# snc98_3x4_Switch-futuba.net
KiCad netlist of a schematic drawn in EAGLE
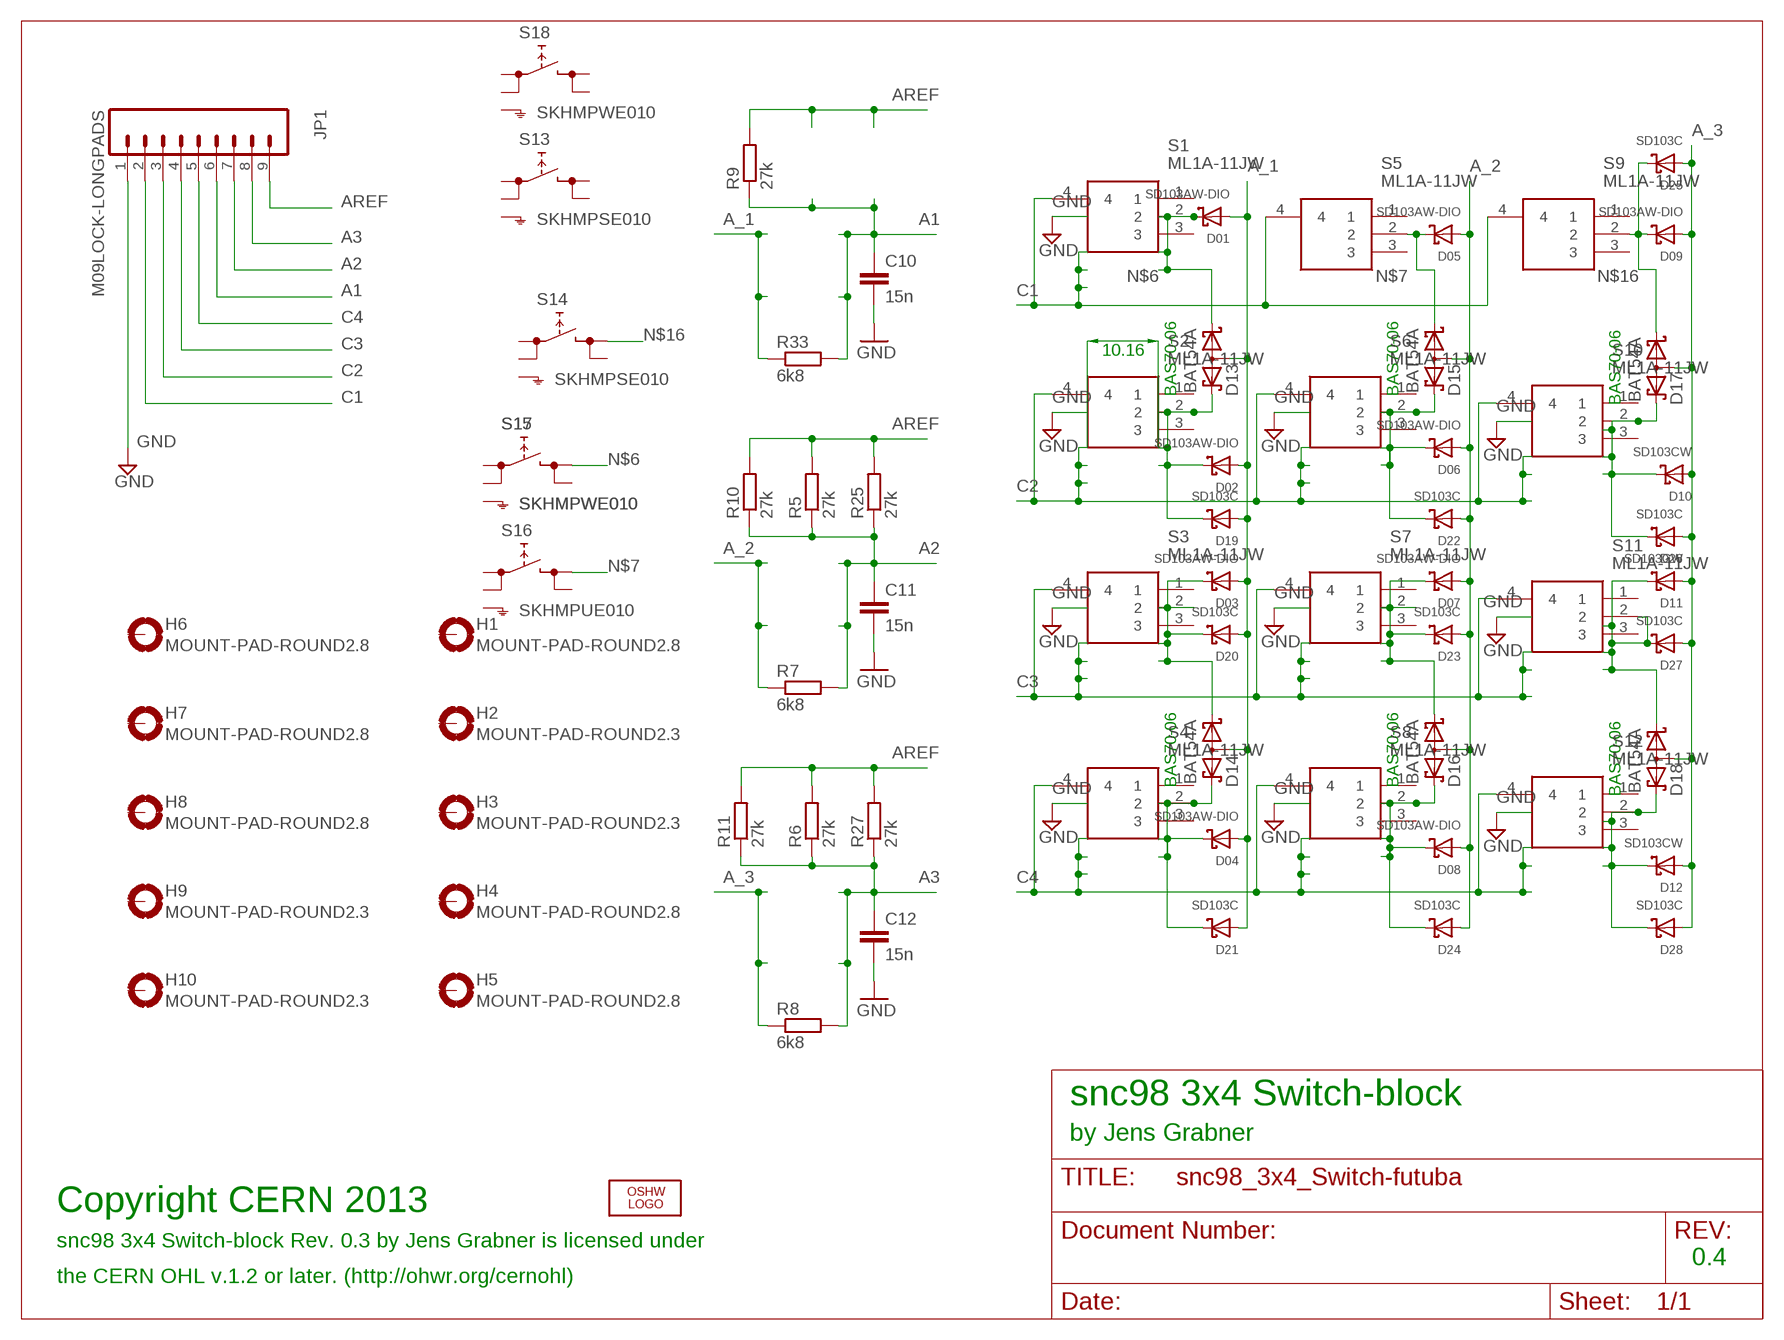
[diagram p0: schematic, sheet 1]

(export (version "E")
  (design (tool "Eeschema 10.0.6"))
  (components
    (comp (ref "C10")
      (value "15n")
      (footprint "eagle-import:C1206K")
      (libsource (lib "eagle-import") (part "C-EUC1206K"))
    )
    (comp (ref "C11")
      (value "15n")
      (footprint "eagle-import:C1206K")
      (libsource (lib "eagle-import") (part "C-EUC1206K"))
    )
    (comp (ref "C12")
      (value "15n")
      (footprint "eagle-import:C1206K")
      (libsource (lib "eagle-import") (part "C-EUC1206K"))
    )
    (comp (ref "D01")
      (value "SD103AW-DIO")
      (footprint "eagle-import:SOD-123F")
      (fields (field (name "MF") "MULTICOMP") (field (name "MPN") "SD103CW-7-F"))
      (libsource (lib "eagle-import") (part "DIODESOD-123F"))
    )
    (comp (ref "D02")
      (value "SD103AW-DIO")
      (footprint "eagle-import:SOD-123F")
      (fields (field (name "MF") "MULTICOMP") (field (name "MPN") "SD103CW-7-F"))
      (libsource (lib "eagle-import") (part "DIODESOD-123F"))
    )
    (comp (ref "D03")
      (value "SD103AW-DIO")
      (footprint "eagle-import:SOD-123F")
      (fields (field (name "MF") "MULTICOMP") (field (name "MPN") "SD103CW-7-F"))
      (libsource (lib "eagle-import") (part "DIODESOD-123F"))
    )
    (comp (ref "D04")
      (value "SD103AW-DIO")
      (footprint "eagle-import:SOD-123F")
      (fields (field (name "MF") "MULTICOMP") (field (name "MPN") "SD103CW-7-F"))
      (libsource (lib "eagle-import") (part "DIODESOD-123F"))
    )
    (comp (ref "D05")
      (value "SD103AW-DIO")
      (footprint "eagle-import:SOD-123F")
      (fields (field (name "MF") "MULTICOMP") (field (name "MPN") "SD103CW-7-F"))
      (libsource (lib "eagle-import") (part "DIODESOD-123F"))
    )
    (comp (ref "D06")
      (value "SD103AW-DIO")
      (footprint "eagle-import:SOD-123F")
      (fields (field (name "MF") "MULTICOMP") (field (name "MPN") "SD103CW-7-F"))
      (libsource (lib "eagle-import") (part "DIODESOD-123F"))
    )
    (comp (ref "D07")
      (value "SD103AW-DIO")
      (footprint "eagle-import:SOD-123F")
      (fields (field (name "MF") "MULTICOMP") (field (name "MPN") "SD103CW-7-F"))
      (libsource (lib "eagle-import") (part "DIODESOD-123F"))
    )
    (comp (ref "D08")
      (value "SD103AW-DIO")
      (footprint "eagle-import:SOD-123F")
      (fields (field (name "MF") "MULTICOMP") (field (name "MPN") "SD103CW-7-F"))
      (libsource (lib "eagle-import") (part "DIODESOD-123F"))
    )
    (comp (ref "D09")
      (value "SD103AW-DIO")
      (footprint "eagle-import:SOD-123F")
      (fields (field (name "MF") "MULTICOMP") (field (name "MPN") "SD103CW-7-F"))
      (libsource (lib "eagle-import") (part "DIODESOD-123F"))
    )
    (comp (ref "D10")
      (value "SD103CW")
      (footprint "eagle-import:SOD-123F")
      (fields (field (name "MF") "MULTICOMP") (field (name "MPN") "SD103CW-7-F"))
      (libsource (lib "eagle-import") (part "DIODESOD-123F"))
    )
    (comp (ref "D11")
      (value "SD103CW")
      (footprint "eagle-import:SOD-123F")
      (fields (field (name "MF") "MULTICOMP") (field (name "MPN") "SD103CW-7-F"))
      (libsource (lib "eagle-import") (part "DIODESOD-123F"))
    )
    (comp (ref "D12")
      (value "SD103CW")
      (footprint "eagle-import:SOD-123F")
      (fields (field (name "MF") "MULTICOMP") (field (name "MPN") "SD103CW-7-F"))
      (libsource (lib "eagle-import") (part "DIODESOD-123F"))
    )
    (comp (ref "D13")
      (value "BAT54A")
      (footprint "eagle-import:SOT23")
      (libsource (lib "eagle-import") (part "BAT54A"))
    )
    (comp (ref "D14")
      (value "BAT54A")
      (footprint "eagle-import:SOT23")
      (libsource (lib "eagle-import") (part "BAT54A"))
    )
    (comp (ref "D15")
      (value "BAT54A")
      (footprint "eagle-import:SOT23")
      (libsource (lib "eagle-import") (part "BAT54A"))
    )
    (comp (ref "D16")
      (value "BAT54A")
      (footprint "eagle-import:SOT23")
      (libsource (lib "eagle-import") (part "BAT54A"))
    )
    (comp (ref "D17")
      (value "BAT54A")
      (footprint "eagle-import:SOT23")
      (libsource (lib "eagle-import") (part "BAT54A"))
    )
    (comp (ref "D18")
      (value "BAT54A")
      (footprint "eagle-import:SOT23")
      (libsource (lib "eagle-import") (part "BAT54A"))
    )
    (comp (ref "D19")
      (value "SD103C")
      (footprint "eagle-import:280MIL-TH")
      (fields (field (name "MF") "MULTICOMP") (field (name "MPN") "SD103CW-7-F"))
      (libsource (lib "eagle-import") (part "DIODE280MIL-TH"))
    )
    (comp (ref "D20")
      (value "SD103C")
      (footprint "eagle-import:280MIL-TH")
      (fields (field (name "MF") "MULTICOMP") (field (name "MPN") "SD103CW-7-F"))
      (libsource (lib "eagle-import") (part "DIODE280MIL-TH"))
    )
    (comp (ref "D21")
      (value "SD103C")
      (footprint "eagle-import:280MIL-TH")
      (fields (field (name "MF") "MULTICOMP") (field (name "MPN") "SD103CW-7-F"))
      (libsource (lib "eagle-import") (part "DIODE280MIL-TH"))
    )
    (comp (ref "D22")
      (value "SD103C")
      (footprint "eagle-import:280MIL-TH")
      (fields (field (name "MF") "MULTICOMP") (field (name "MPN") "SD103CW-7-F"))
      (libsource (lib "eagle-import") (part "DIODE280MIL-TH"))
    )
    (comp (ref "D23")
      (value "SD103C")
      (footprint "eagle-import:280MIL-TH")
      (fields (field (name "MF") "MULTICOMP") (field (name "MPN") "SD103CW-7-F"))
      (libsource (lib "eagle-import") (part "DIODE280MIL-TH"))
    )
    (comp (ref "D24")
      (value "SD103C")
      (footprint "eagle-import:280MIL-TH")
      (fields (field (name "MF") "MULTICOMP") (field (name "MPN") "SD103CW-7-F"))
      (libsource (lib "eagle-import") (part "DIODE280MIL-TH"))
    )
    (comp (ref "D25")
      (value "SD103C")
      (footprint "eagle-import:280MIL-TH")
      (fields (field (name "MF") "MULTICOMP") (field (name "MPN") "SD103CW-7-F"))
      (libsource (lib "eagle-import") (part "DIODE280MIL-TH"))
    )
    (comp (ref "D26")
      (value "SD103C")
      (footprint "eagle-import:280MIL-TH")
      (fields (field (name "MF") "MULTICOMP") (field (name "MPN") "SD103CW-7-F"))
      (libsource (lib "eagle-import") (part "DIODE280MIL-TH"))
    )
    (comp (ref "D27")
      (value "SD103C")
      (footprint "eagle-import:280MIL-TH")
      (fields (field (name "MF") "MULTICOMP") (field (name "MPN") "SD103CW-7-F"))
      (libsource (lib "eagle-import") (part "DIODE280MIL-TH"))
    )
    (comp (ref "D28")
      (value "SD103C")
      (footprint "eagle-import:280MIL-TH")
      (fields (field (name "MF") "MULTICOMP") (field (name "MPN") "SD103CW-7-F"))
      (libsource (lib "eagle-import") (part "DIODE280MIL-TH"))
    )
    (comp (ref "H1")
      (value "MOUNT-PAD-ROUND2.8")
      (footprint "eagle-import:2,8-PAD")
      (libsource (lib "eagle-import") (part "MOUNT-PAD-ROUND2.8"))
    )
    (comp (ref "H2")
      (value "MOUNT-PAD-ROUND2.3")
      (footprint "eagle-import:2,3-PAD")
      (libsource (lib "eagle-import") (part "MOUNT-PAD-ROUND2.3"))
    )
    (comp (ref "H3")
      (value "MOUNT-PAD-ROUND2.3")
      (footprint "eagle-import:2,3-PAD")
      (libsource (lib "eagle-import") (part "MOUNT-PAD-ROUND2.3"))
    )
    (comp (ref "H4")
      (value "MOUNT-PAD-ROUND2.8")
      (footprint "eagle-import:2,8-PAD")
      (libsource (lib "eagle-import") (part "MOUNT-PAD-ROUND2.8"))
    )
    (comp (ref "H5")
      (value "MOUNT-PAD-ROUND2.8")
      (footprint "eagle-import:2,8-PAD")
      (libsource (lib "eagle-import") (part "MOUNT-PAD-ROUND2.8"))
    )
    (comp (ref "H6")
      (value "MOUNT-PAD-ROUND2.8")
      (footprint "eagle-import:2,8-PAD")
      (libsource (lib "eagle-import") (part "MOUNT-PAD-ROUND2.8"))
    )
    (comp (ref "H7")
      (value "MOUNT-PAD-ROUND2.8")
      (footprint "eagle-import:2,8-PAD")
      (libsource (lib "eagle-import") (part "MOUNT-PAD-ROUND2.8"))
    )
    (comp (ref "H8")
      (value "MOUNT-PAD-ROUND2.8")
      (footprint "eagle-import:2,8-PAD")
      (libsource (lib "eagle-import") (part "MOUNT-PAD-ROUND2.8"))
    )
    (comp (ref "H9")
      (value "MOUNT-PAD-ROUND2.3")
      (footprint "eagle-import:2,3-PAD")
      (libsource (lib "eagle-import") (part "MOUNT-PAD-ROUND2.3"))
    )
    (comp (ref "H10")
      (value "MOUNT-PAD-ROUND2.3")
      (footprint "eagle-import:2,3-PAD")
      (libsource (lib "eagle-import") (part "MOUNT-PAD-ROUND2.3"))
    )
    (comp (ref "JP1")
      (value "M09LOCK-LONGPADS")
      (footprint "eagle-import:1X09_LOCK_LONGPADS")
      (libsource (lib "eagle-import") (part "M09LOCK-LONGPADS"))
    )
    (comp (ref "LOGO1")
      (value "OSHW_LOGO_8MILX0150-NT")
      (footprint "eagle-import:OSHW_8X150_NOTEXT")
      (libsource (lib "eagle-import") (part "OSHW_LOGO_8MILX0150-NT"))
    )
    (comp (ref "R5")
      (value "27k")
      (footprint "eagle-import:R1206")
      (libsource (lib "eagle-import") (part "R-EU_R1206"))
    )
    (comp (ref "R6")
      (value "27k")
      (footprint "eagle-import:R1206")
      (libsource (lib "eagle-import") (part "R-EU_R1206"))
    )
    (comp (ref "R7")
      (value "6k8")
      (footprint "eagle-import:M0805")
      (libsource (lib "eagle-import") (part "R-EU_M0805"))
    )
    (comp (ref "R8")
      (value "6k8")
      (footprint "eagle-import:M0805")
      (libsource (lib "eagle-import") (part "R-EU_M0805"))
    )
    (comp (ref "R9")
      (value "27k")
      (footprint "eagle-import:M0805")
      (libsource (lib "eagle-import") (part "R-EU_M0805"))
    )
    (comp (ref "R10")
      (value "27k")
      (footprint "eagle-import:M0805")
      (libsource (lib "eagle-import") (part "R-EU_M0805"))
    )
    (comp (ref "R11")
      (value "27k")
      (footprint "eagle-import:M0805")
      (libsource (lib "eagle-import") (part "R-EU_M0805"))
    )
    (comp (ref "R25")
      (value "27k")
      (footprint "eagle-import:0204_5")
      (libsource (lib "eagle-import") (part "R-EU_0204/5"))
    )
    (comp (ref "R27")
      (value "27k")
      (footprint "eagle-import:0204_5")
      (libsource (lib "eagle-import") (part "R-EU_0204/5"))
    )
    (comp (ref "R33")
      (value "6k8")
      (footprint "eagle-import:M0805")
      (libsource (lib "eagle-import") (part "R-EU_M0805"))
    )
    (comp (ref "S1")
      (value "ML1A-11JW")
      (footprint "eagle-import:ML1A11JW")
      (fields (field (name "MOUSER_PART_NUMBER") "540-ML1A-11JW"))
      (libsource (lib "eagle-import") (part "ML1A-11JW"))
    )
    (comp (ref "S2")
      (value "ML1A-11JW")
      (footprint "eagle-import:ML1A11JW")
      (fields (field (name "MOUSER_PART_NUMBER") "540-ML1A-11JW"))
      (libsource (lib "eagle-import") (part "ML1A-11JW"))
    )
    (comp (ref "S3")
      (value "ML1A-11JW")
      (footprint "eagle-import:ML1A11JW")
      (fields (field (name "MOUSER_PART_NUMBER") "540-ML1A-11JW"))
      (libsource (lib "eagle-import") (part "ML1A-11JW"))
    )
    (comp (ref "S4")
      (value "ML1A-11JW")
      (footprint "eagle-import:ML1A11JW")
      (fields (field (name "MOUSER_PART_NUMBER") "540-ML1A-11JW"))
      (libsource (lib "eagle-import") (part "ML1A-11JW"))
    )
    (comp (ref "S5")
      (value "ML1A-11JW")
      (footprint "eagle-import:ML1A11JW")
      (fields (field (name "MOUSER_PART_NUMBER") "540-ML1A-11JW"))
      (libsource (lib "eagle-import") (part "ML1A-11JW"))
    )
    (comp (ref "S6")
      (value "ML1A-11JW")
      (footprint "eagle-import:ML1A11JW")
      (fields (field (name "MOUSER_PART_NUMBER") "540-ML1A-11JW"))
      (libsource (lib "eagle-import") (part "ML1A-11JW"))
    )
    (comp (ref "S7")
      (value "ML1A-11JW")
      (footprint "eagle-import:ML1A11JW")
      (fields (field (name "MOUSER_PART_NUMBER") "540-ML1A-11JW"))
      (libsource (lib "eagle-import") (part "ML1A-11JW"))
    )
    (comp (ref "S8")
      (value "ML1A-11JW")
      (footprint "eagle-import:ML1A11JW")
      (fields (field (name "MOUSER_PART_NUMBER") "540-ML1A-11JW"))
      (libsource (lib "eagle-import") (part "ML1A-11JW"))
    )
    (comp (ref "S9")
      (value "ML1A-11JW")
      (footprint "eagle-import:ML1A11JW")
      (fields (field (name "MOUSER_PART_NUMBER") "540-ML1A-11JW"))
      (libsource (lib "eagle-import") (part "ML1A-11JW"))
    )
    (comp (ref "S10")
      (value "ML1A-11JW")
      (footprint "eagle-import:ML1A11JW")
      (fields (field (name "MOUSER_PART_NUMBER") "540-ML1A-11JW"))
      (libsource (lib "eagle-import") (part "ML1A-11JW"))
    )
    (comp (ref "S11")
      (value "ML1A-11JW")
      (footprint "eagle-import:ML1A11JW")
      (fields (field (name "MOUSER_PART_NUMBER") "540-ML1A-11JW"))
      (libsource (lib "eagle-import") (part "ML1A-11JW"))
    )
    (comp (ref "S12")
      (value "ML1A-11JW")
      (footprint "eagle-import:ML1A11JW")
      (fields (field (name "MOUSER_PART_NUMBER") "540-ML1A-11JW"))
      (libsource (lib "eagle-import") (part "ML1A-11JW"))
    )
    (comp (ref "S13")
      (value "SKHMPSE010")
      (footprint "eagle-import:SKHMPXE010")
      (libsource (lib "eagle-import") (part "SKHMPE010S"))
    )
    (comp (ref "S14")
      (value "SKHMPSE010")
      (footprint "eagle-import:SKHMPXE010")
      (libsource (lib "eagle-import") (part "SKHMPE010S"))
    )
    (comp (ref "S15")
      (value "SKHMPWE010")
      (footprint "eagle-import:SKHMPXE010")
      (libsource (lib "eagle-import") (part "SKHMPE010W"))
    )
    (comp (ref "S16")
      (value "SKHMPUE010")
      (footprint "eagle-import:SKHMPXE010")
      (libsource (lib "eagle-import") (part "SKHMPE010U"))
    )
    (comp (ref "S17")
      (value "SKHMPWE010")
      (footprint "eagle-import:SKHMPXE010")
      (libsource (lib "eagle-import") (part "SKHMPE010W"))
    )
    (comp (ref "S18")
      (value "SKHMPWE010")
      (footprint "eagle-import:SKHMPXE010")
      (libsource (lib "eagle-import") (part "SKHMPE010W"))
    )
  )
  (nets
    (net (code "1") (name "/A1") (class "Default")
      (node (ref "C10") (pin "1") (pinfunction "1_1") (pintype "passive"))
      (node (ref "JP1") (pin "6") (pinfunction "6_6") (pintype "passive"))
      (node (ref "R33") (pin "2") (pinfunction "2_2") (pintype "passive"))
      (node (ref "R9") (pin "1") (pinfunction "1_1") (pintype "passive"))
    )
    (net (code "2") (name "/A2") (class "Default")
      (node (ref "C11") (pin "1") (pinfunction "1_1") (pintype "passive"))
      (node (ref "JP1") (pin "7") (pinfunction "7_7") (pintype "passive"))
      (node (ref "R10") (pin "1") (pinfunction "1_1") (pintype "passive"))
      (node (ref "R25") (pin "1") (pinfunction "1_1") (pintype "passive"))
      (node (ref "R5") (pin "1") (pinfunction "1_1") (pintype "passive"))
      (node (ref "R7") (pin "2") (pinfunction "2_2") (pintype "passive"))
    )
    (net (code "3") (name "/A3") (class "Default")
      (node (ref "C12") (pin "1") (pinfunction "1_1") (pintype "passive"))
      (node (ref "JP1") (pin "8") (pinfunction "8_8") (pintype "passive"))
      (node (ref "R11") (pin "1") (pinfunction "1_1") (pintype "passive"))
      (node (ref "R27") (pin "1") (pinfunction "1_1") (pintype "passive"))
      (node (ref "R6") (pin "1") (pinfunction "1_1") (pintype "passive"))
      (node (ref "R8") (pin "2") (pinfunction "2_2") (pintype "passive"))
    )
    (net (code "4") (name "/AREF") (class "Default")
      (node (ref "JP1") (pin "9") (pinfunction "9_9") (pintype "passive"))
      (node (ref "R10") (pin "2") (pinfunction "2_2") (pintype "passive"))
      (node (ref "R11") (pin "2") (pinfunction "2_2") (pintype "passive"))
      (node (ref "R25") (pin "2") (pinfunction "2_2") (pintype "passive"))
      (node (ref "R27") (pin "2") (pinfunction "2_2") (pintype "passive"))
      (node (ref "R5") (pin "2") (pinfunction "2_2") (pintype "passive"))
      (node (ref "R6") (pin "2") (pinfunction "2_2") (pintype "passive"))
      (node (ref "R9") (pin "2") (pinfunction "2_2") (pintype "passive"))
    )
    (net (code "5") (name "/A_1") (class "Default")
      (node (ref "D01") (pin "A") (pinfunction "A_A") (pintype "passive"))
      (node (ref "D02") (pin "A") (pinfunction "A_A") (pintype "passive"))
      (node (ref "D03") (pin "A") (pinfunction "A_A") (pintype "passive"))
      (node (ref "D04") (pin "A") (pinfunction "A_A") (pintype "passive"))
      (node (ref "D13") (pin "3") (pinfunction "AA_3") (pintype "passive"))
      (node (ref "D14") (pin "3") (pinfunction "AA_3") (pintype "passive"))
      (node (ref "D19") (pin "P$1") (pinfunction "A_P$1") (pintype "passive"))
      (node (ref "D20") (pin "P$1") (pinfunction "A_P$1") (pintype "passive"))
      (node (ref "D21") (pin "P$1") (pinfunction "A_P$1") (pintype "passive"))
      (node (ref "R33") (pin "1") (pinfunction "1_1") (pintype "passive"))
    )
    (net (code "6") (name "/A_2") (class "Default")
      (node (ref "D05") (pin "A") (pinfunction "A_A") (pintype "passive"))
      (node (ref "D06") (pin "A") (pinfunction "A_A") (pintype "passive"))
      (node (ref "D07") (pin "A") (pinfunction "A_A") (pintype "passive"))
      (node (ref "D08") (pin "A") (pinfunction "A_A") (pintype "passive"))
      (node (ref "D15") (pin "3") (pinfunction "AA_3") (pintype "passive"))
      (node (ref "D16") (pin "3") (pinfunction "AA_3") (pintype "passive"))
      (node (ref "D22") (pin "P$1") (pinfunction "A_P$1") (pintype "passive"))
      (node (ref "D23") (pin "P$1") (pinfunction "A_P$1") (pintype "passive"))
      (node (ref "D24") (pin "P$1") (pinfunction "A_P$1") (pintype "passive"))
      (node (ref "R7") (pin "1") (pinfunction "1_1") (pintype "passive"))
    )
    (net (code "7") (name "/A_3") (class "Default")
      (node (ref "D09") (pin "A") (pinfunction "A_A") (pintype "passive"))
      (node (ref "D10") (pin "A") (pinfunction "A_A") (pintype "passive"))
      (node (ref "D11") (pin "A") (pinfunction "A_A") (pintype "passive"))
      (node (ref "D12") (pin "A") (pinfunction "A_A") (pintype "passive"))
      (node (ref "D17") (pin "3") (pinfunction "AA_3") (pintype "passive"))
      (node (ref "D18") (pin "3") (pinfunction "AA_3") (pintype "passive"))
      (node (ref "D25") (pin "P$1") (pinfunction "A_P$1") (pintype "passive"))
      (node (ref "D26") (pin "P$1") (pinfunction "A_P$1") (pintype "passive"))
      (node (ref "D27") (pin "P$1") (pinfunction "A_P$1") (pintype "passive"))
      (node (ref "D28") (pin "P$1") (pinfunction "A_P$1") (pintype "passive"))
      (node (ref "R8") (pin "1") (pinfunction "1_1") (pintype "passive"))
    )
    (net (code "8") (name "/C1") (class "Default")
      (node (ref "JP1") (pin "2") (pinfunction "2_2") (pintype "passive"))
      (node (ref "S1") (pin "4") (pinfunction "4_4") (pintype "bidirectional"))
      (node (ref "S5") (pin "4") (pinfunction "4_4") (pintype "bidirectional"))
      (node (ref "S9") (pin "4") (pinfunction "4_4") (pintype "bidirectional"))
    )
    (net (code "9") (name "/C2") (class "Default")
      (node (ref "JP1") (pin "3") (pinfunction "3_3") (pintype "passive"))
      (node (ref "S10") (pin "4") (pinfunction "4_4") (pintype "bidirectional"))
      (node (ref "S2") (pin "4") (pinfunction "4_4") (pintype "bidirectional"))
      (node (ref "S6") (pin "4") (pinfunction "4_4") (pintype "bidirectional"))
    )
    (net (code "10") (name "/C3") (class "Default")
      (node (ref "JP1") (pin "4") (pinfunction "4_4") (pintype "passive"))
      (node (ref "S11") (pin "4") (pinfunction "4_4") (pintype "bidirectional"))
      (node (ref "S3") (pin "4") (pinfunction "4_4") (pintype "bidirectional"))
      (node (ref "S7") (pin "4") (pinfunction "4_4") (pintype "bidirectional"))
    )
    (net (code "11") (name "/C4") (class "Default")
      (node (ref "JP1") (pin "5") (pinfunction "5_5") (pintype "passive"))
      (node (ref "S12") (pin "4") (pinfunction "4_4") (pintype "bidirectional"))
      (node (ref "S4") (pin "4") (pinfunction "4_4") (pintype "bidirectional"))
      (node (ref "S8") (pin "4") (pinfunction "4_4") (pintype "bidirectional"))
    )
    (net (code "12") (name "/N$6") (class "Default")
      (node (ref "D01") (pin "C") (pinfunction "C_C") (pintype "passive"))
      (node (ref "D13") (pin "1") (pinfunction "K1_1") (pintype "passive"))
      (node (ref "S1") (pin "2") (pinfunction "2_2") (pintype "bidirectional"))
      (node (ref "S15") (pin "3") (pinfunction "2.1_3") (pintype "passive"))
      (node (ref "S17") (pin "3") (pinfunction "2.1_3") (pintype "passive"))
    )
    (net (code "13") (name "/N$7") (class "Default")
      (node (ref "D05") (pin "C") (pinfunction "C_C") (pintype "passive"))
      (node (ref "D15") (pin "1") (pinfunction "K1_1") (pintype "passive"))
      (node (ref "S16") (pin "3") (pinfunction "2.1_3") (pintype "passive"))
      (node (ref "S5") (pin "2") (pinfunction "2_2") (pintype "bidirectional"))
    )
    (net (code "14") (name "/N$16") (class "Default")
      (node (ref "D09") (pin "C") (pinfunction "C_C") (pintype "passive"))
      (node (ref "D17") (pin "1") (pinfunction "K1_1") (pintype "passive"))
      (node (ref "D25") (pin "P$2") (pinfunction "C_P$2") (pintype "passive"))
      (node (ref "S14") (pin "3") (pinfunction "2.1_3") (pintype "passive"))
      (node (ref "S9") (pin "2") (pinfunction "2_2") (pintype "bidirectional"))
    )
    (net (code "15") (name "GND") (class "Default")
      (node (ref "C10") (pin "2") (pinfunction "2_2") (pintype "passive"))
      (node (ref "C11") (pin "2") (pinfunction "2_2") (pintype "passive"))
      (node (ref "C12") (pin "2") (pinfunction "2_2") (pintype "passive"))
      (node (ref "JP1") (pin "1") (pinfunction "1_1") (pintype "passive"))
    )
    (net (code "16") (name "Net-(D13-K2)") (class "Default")
      (node (ref "D02") (pin "C") (pinfunction "C_C") (pintype "passive"))
      (node (ref "D13") (pin "2") (pinfunction "K2_2") (pintype "passive"))
      (node (ref "D19") (pin "P$2") (pinfunction "C_P$2") (pintype "passive"))
      (node (ref "S2") (pin "2") (pinfunction "2_2") (pintype "bidirectional"))
    )
    (net (code "17") (name "Net-(D14-K1)") (class "Default")
      (node (ref "D03") (pin "C") (pinfunction "C_C") (pintype "passive"))
      (node (ref "D14") (pin "1") (pinfunction "K1_1") (pintype "passive"))
      (node (ref "D20") (pin "P$2") (pinfunction "C_P$2") (pintype "passive"))
      (node (ref "S3") (pin "2") (pinfunction "2_2") (pintype "bidirectional"))
    )
    (net (code "18") (name "Net-(D14-K2)") (class "Default")
      (node (ref "D04") (pin "C") (pinfunction "C_C") (pintype "passive"))
      (node (ref "D14") (pin "2") (pinfunction "K2_2") (pintype "passive"))
      (node (ref "D21") (pin "P$2") (pinfunction "C_P$2") (pintype "passive"))
      (node (ref "S4") (pin "2") (pinfunction "2_2") (pintype "bidirectional"))
    )
    (net (code "19") (name "Net-(D15-K2)") (class "Default")
      (node (ref "D06") (pin "C") (pinfunction "C_C") (pintype "passive"))
      (node (ref "D15") (pin "2") (pinfunction "K2_2") (pintype "passive"))
      (node (ref "D22") (pin "P$2") (pinfunction "C_P$2") (pintype "passive"))
      (node (ref "S6") (pin "2") (pinfunction "2_2") (pintype "bidirectional"))
    )
    (net (code "20") (name "Net-(D16-K1)") (class "Default")
      (node (ref "D07") (pin "C") (pinfunction "C_C") (pintype "passive"))
      (node (ref "D16") (pin "1") (pinfunction "K1_1") (pintype "passive"))
      (node (ref "D23") (pin "P$2") (pinfunction "C_P$2") (pintype "passive"))
      (node (ref "S7") (pin "2") (pinfunction "2_2") (pintype "bidirectional"))
    )
    (net (code "21") (name "Net-(D16-K2)") (class "Default")
      (node (ref "D08") (pin "C") (pinfunction "C_C") (pintype "passive"))
      (node (ref "D16") (pin "2") (pinfunction "K2_2") (pintype "passive"))
      (node (ref "D24") (pin "P$2") (pinfunction "C_P$2") (pintype "passive"))
      (node (ref "S8") (pin "2") (pinfunction "2_2") (pintype "bidirectional"))
    )
    (net (code "22") (name "Net-(D17-K2)") (class "Default")
      (node (ref "D10") (pin "C") (pinfunction "C_C") (pintype "passive"))
      (node (ref "D17") (pin "2") (pinfunction "K2_2") (pintype "passive"))
      (node (ref "D26") (pin "P$2") (pinfunction "C_P$2") (pintype "passive"))
      (node (ref "S10") (pin "2") (pinfunction "2_2") (pintype "bidirectional"))
    )
    (net (code "23") (name "Net-(D18-K1)") (class "Default")
      (node (ref "D11") (pin "C") (pinfunction "C_C") (pintype "passive"))
      (node (ref "D18") (pin "1") (pinfunction "K1_1") (pintype "passive"))
      (node (ref "D27") (pin "P$2") (pinfunction "C_P$2") (pintype "passive"))
      (node (ref "S11") (pin "2") (pinfunction "2_2") (pintype "bidirectional"))
    )
    (net (code "24") (name "Net-(D18-K2)") (class "Default")
      (node (ref "D12") (pin "C") (pinfunction "C_C") (pintype "passive"))
      (node (ref "D18") (pin "2") (pinfunction "K2_2") (pintype "passive"))
      (node (ref "D28") (pin "P$2") (pinfunction "C_P$2") (pintype "passive"))
      (node (ref "S12") (pin "2") (pinfunction "2_2") (pintype "bidirectional"))
    )
    (net (code "25") (name "Net-(S15-1.1)") (class "Default")
      (node (ref "S15") (pin "1") (pinfunction "1.1_1") (pintype "passive"))
      (node (ref "S17") (pin "1") (pinfunction "1.1_1") (pintype "passive"))
    )
    (net (code "26") (name "Net-(S15-1.2)") (class "Default")
      (node (ref "S15") (pin "2") (pinfunction "1.2_2") (pintype "passive"))
      (node (ref "S17") (pin "2") (pinfunction "1.2_2") (pintype "passive"))
    )
    (net (code "27") (name "Net-(S15-2.2)") (class "Default")
      (node (ref "S15") (pin "4") (pinfunction "2.2_4") (pintype "passive"))
      (node (ref "S17") (pin "4") (pinfunction "2.2_4") (pintype "passive"))
    )
    (net (code "28") (name "Net-(S15-SH)") (class "Default")
      (node (ref "S15") (pin "5") (pinfunction "SH_5") (pintype "passive"))
      (node (ref "S17") (pin "5") (pinfunction "SH_5") (pintype "passive"))
    )
    (net (code "29") (name "unconnected-(H1-MOUNT-PadB2,8)") (class "Default")
      (node (ref "H1") (pin "B2,8") (pinfunction "MOUNT_B2,8") (pintype "passive"))
    )
    (net (code "30") (name "unconnected-(H2-MOUNT-PadB2,8)") (class "Default")
      (node (ref "H2") (pin "B2,8") (pinfunction "MOUNT_B2,8") (pintype "passive"))
    )
    (net (code "31") (name "unconnected-(H3-MOUNT-PadB2,8)") (class "Default")
      (node (ref "H3") (pin "B2,8") (pinfunction "MOUNT_B2,8") (pintype "passive"))
    )
    (net (code "32") (name "unconnected-(H4-MOUNT-PadB2,8)") (class "Default")
      (node (ref "H4") (pin "B2,8") (pinfunction "MOUNT_B2,8") (pintype "passive"))
    )
    (net (code "33") (name "unconnected-(H5-MOUNT-PadB2,8)") (class "Default")
      (node (ref "H5") (pin "B2,8") (pinfunction "MOUNT_B2,8") (pintype "passive"))
    )
    (net (code "34") (name "unconnected-(H6-MOUNT-PadB2,8)") (class "Default")
      (node (ref "H6") (pin "B2,8") (pinfunction "MOUNT_B2,8") (pintype "passive"))
    )
    (net (code "35") (name "unconnected-(H7-MOUNT-PadB2,8)") (class "Default")
      (node (ref "H7") (pin "B2,8") (pinfunction "MOUNT_B2,8") (pintype "passive"))
    )
    (net (code "36") (name "unconnected-(H8-MOUNT-PadB2,8)") (class "Default")
      (node (ref "H8") (pin "B2,8") (pinfunction "MOUNT_B2,8") (pintype "passive"))
    )
    (net (code "37") (name "unconnected-(H9-MOUNT-PadB2,8)") (class "Default")
      (node (ref "H9") (pin "B2,8") (pinfunction "MOUNT_B2,8") (pintype "passive"))
    )
    (net (code "38") (name "unconnected-(H10-MOUNT-PadB2,8)") (class "Default")
      (node (ref "H10") (pin "B2,8") (pinfunction "MOUNT_B2,8") (pintype "passive"))
    )
    (net (code "39") (name "unconnected-(S1-Pad1)") (class "Default")
      (node (ref "S1") (pin "1") (pinfunction "1_1") (pintype "bidirectional"))
    )
    (net (code "40") (name "unconnected-(S1-Pad3)") (class "Default")
      (node (ref "S1") (pin "3") (pinfunction "3_3") (pintype "bidirectional"))
    )
    (net (code "41") (name "unconnected-(S2-Pad1)") (class "Default")
      (node (ref "S2") (pin "1") (pinfunction "1_1") (pintype "bidirectional"))
    )
    (net (code "42") (name "unconnected-(S2-Pad3)") (class "Default")
      (node (ref "S2") (pin "3") (pinfunction "3_3") (pintype "bidirectional"))
    )
    (net (code "43") (name "unconnected-(S3-Pad1)") (class "Default")
      (node (ref "S3") (pin "1") (pinfunction "1_1") (pintype "bidirectional"))
    )
    (net (code "44") (name "unconnected-(S3-Pad3)") (class "Default")
      (node (ref "S3") (pin "3") (pinfunction "3_3") (pintype "bidirectional"))
    )
    (net (code "45") (name "unconnected-(S4-Pad1)") (class "Default")
      (node (ref "S4") (pin "1") (pinfunction "1_1") (pintype "bidirectional"))
    )
    (net (code "46") (name "unconnected-(S4-Pad3)") (class "Default")
      (node (ref "S4") (pin "3") (pinfunction "3_3") (pintype "bidirectional"))
    )
    (net (code "47") (name "unconnected-(S5-Pad1)") (class "Default")
      (node (ref "S5") (pin "1") (pinfunction "1_1") (pintype "bidirectional"))
    )
    (net (code "48") (name "unconnected-(S5-Pad3)") (class "Default")
      (node (ref "S5") (pin "3") (pinfunction "3_3") (pintype "bidirectional"))
    )
    (net (code "49") (name "unconnected-(S6-Pad1)") (class "Default")
      (node (ref "S6") (pin "1") (pinfunction "1_1") (pintype "bidirectional"))
    )
    (net (code "50") (name "unconnected-(S6-Pad3)") (class "Default")
      (node (ref "S6") (pin "3") (pinfunction "3_3") (pintype "bidirectional"))
    )
    (net (code "51") (name "unconnected-(S7-Pad1)") (class "Default")
      (node (ref "S7") (pin "1") (pinfunction "1_1") (pintype "bidirectional"))
    )
    (net (code "52") (name "unconnected-(S7-Pad3)") (class "Default")
      (node (ref "S7") (pin "3") (pinfunction "3_3") (pintype "bidirectional"))
    )
    (net (code "53") (name "unconnected-(S8-Pad1)") (class "Default")
      (node (ref "S8") (pin "1") (pinfunction "1_1") (pintype "bidirectional"))
    )
    (net (code "54") (name "unconnected-(S8-Pad3)") (class "Default")
      (node (ref "S8") (pin "3") (pinfunction "3_3") (pintype "bidirectional"))
    )
    (net (code "55") (name "unconnected-(S9-Pad1)") (class "Default")
      (node (ref "S9") (pin "1") (pinfunction "1_1") (pintype "bidirectional"))
    )
    (net (code "56") (name "unconnected-(S9-Pad3)") (class "Default")
      (node (ref "S9") (pin "3") (pinfunction "3_3") (pintype "bidirectional"))
    )
    (net (code "57") (name "unconnected-(S10-Pad1)") (class "Default")
      (node (ref "S10") (pin "1") (pinfunction "1_1") (pintype "bidirectional"))
    )
    (net (code "58") (name "unconnected-(S10-Pad3)") (class "Default")
      (node (ref "S10") (pin "3") (pinfunction "3_3") (pintype "bidirectional"))
    )
    (net (code "59") (name "unconnected-(S11-Pad1)") (class "Default")
      (node (ref "S11") (pin "1") (pinfunction "1_1") (pintype "bidirectional"))
    )
    (net (code "60") (name "unconnected-(S11-Pad3)") (class "Default")
      (node (ref "S11") (pin "3") (pinfunction "3_3") (pintype "bidirectional"))
    )
    (net (code "61") (name "unconnected-(S12-Pad1)") (class "Default")
      (node (ref "S12") (pin "1") (pinfunction "1_1") (pintype "bidirectional"))
    )
    (net (code "62") (name "unconnected-(S12-Pad3)") (class "Default")
      (node (ref "S12") (pin "3") (pinfunction "3_3") (pintype "bidirectional"))
    )
    (net (code "63") (name "unconnected-(S13-1.1-Pad1)") (class "Default")
      (node (ref "S13") (pin "1") (pinfunction "1.1_1") (pintype "passive"))
    )
    (net (code "64") (name "unconnected-(S13-1.2-Pad2)") (class "Default")
      (node (ref "S13") (pin "2") (pinfunction "1.2_2") (pintype "passive"))
    )
    (net (code "65") (name "unconnected-(S13-2.1-Pad3)") (class "Default")
      (node (ref "S13") (pin "3") (pinfunction "2.1_3") (pintype "passive"))
    )
    (net (code "66") (name "unconnected-(S13-2.2-Pad4)") (class "Default")
      (node (ref "S13") (pin "4") (pinfunction "2.2_4") (pintype "passive"))
    )
    (net (code "67") (name "unconnected-(S13-SH-Pad5)") (class "Default")
      (node (ref "S13") (pin "5") (pinfunction "SH_5") (pintype "passive"))
    )
    (net (code "68") (name "unconnected-(S14-1.1-Pad1)") (class "Default")
      (node (ref "S14") (pin "1") (pinfunction "1.1_1") (pintype "passive"))
    )
    (net (code "69") (name "unconnected-(S14-1.2-Pad2)") (class "Default")
      (node (ref "S14") (pin "2") (pinfunction "1.2_2") (pintype "passive"))
    )
    (net (code "70") (name "unconnected-(S14-2.2-Pad4)") (class "Default")
      (node (ref "S14") (pin "4") (pinfunction "2.2_4") (pintype "passive"))
    )
    (net (code "71") (name "unconnected-(S14-SH-Pad5)") (class "Default")
      (node (ref "S14") (pin "5") (pinfunction "SH_5") (pintype "passive"))
    )
    (net (code "72") (name "unconnected-(S16-1.1-Pad1)") (class "Default")
      (node (ref "S16") (pin "1") (pinfunction "1.1_1") (pintype "passive"))
    )
    (net (code "73") (name "unconnected-(S16-1.2-Pad2)") (class "Default")
      (node (ref "S16") (pin "2") (pinfunction "1.2_2") (pintype "passive"))
    )
    (net (code "74") (name "unconnected-(S16-2.2-Pad4)") (class "Default")
      (node (ref "S16") (pin "4") (pinfunction "2.2_4") (pintype "passive"))
    )
    (net (code "75") (name "unconnected-(S16-SH-Pad5)") (class "Default")
      (node (ref "S16") (pin "5") (pinfunction "SH_5") (pintype "passive"))
    )
    (net (code "76") (name "unconnected-(S18-1.1-Pad1)") (class "Default")
      (node (ref "S18") (pin "1") (pinfunction "1.1_1") (pintype "passive"))
    )
    (net (code "77") (name "unconnected-(S18-1.2-Pad2)") (class "Default")
      (node (ref "S18") (pin "2") (pinfunction "1.2_2") (pintype "passive"))
    )
    (net (code "78") (name "unconnected-(S18-2.1-Pad3)") (class "Default")
      (node (ref "S18") (pin "3") (pinfunction "2.1_3") (pintype "passive"))
    )
    (net (code "79") (name "unconnected-(S18-2.2-Pad4)") (class "Default")
      (node (ref "S18") (pin "4") (pinfunction "2.2_4") (pintype "passive"))
    )
    (net (code "80") (name "unconnected-(S18-SH-Pad5)") (class "Default")
      (node (ref "S18") (pin "5") (pinfunction "SH_5") (pintype "passive"))
    )
  )
)
